# Trottinette_Connexion_PCB.net
KiCad netlist of a schematic drawn in Altium Designer
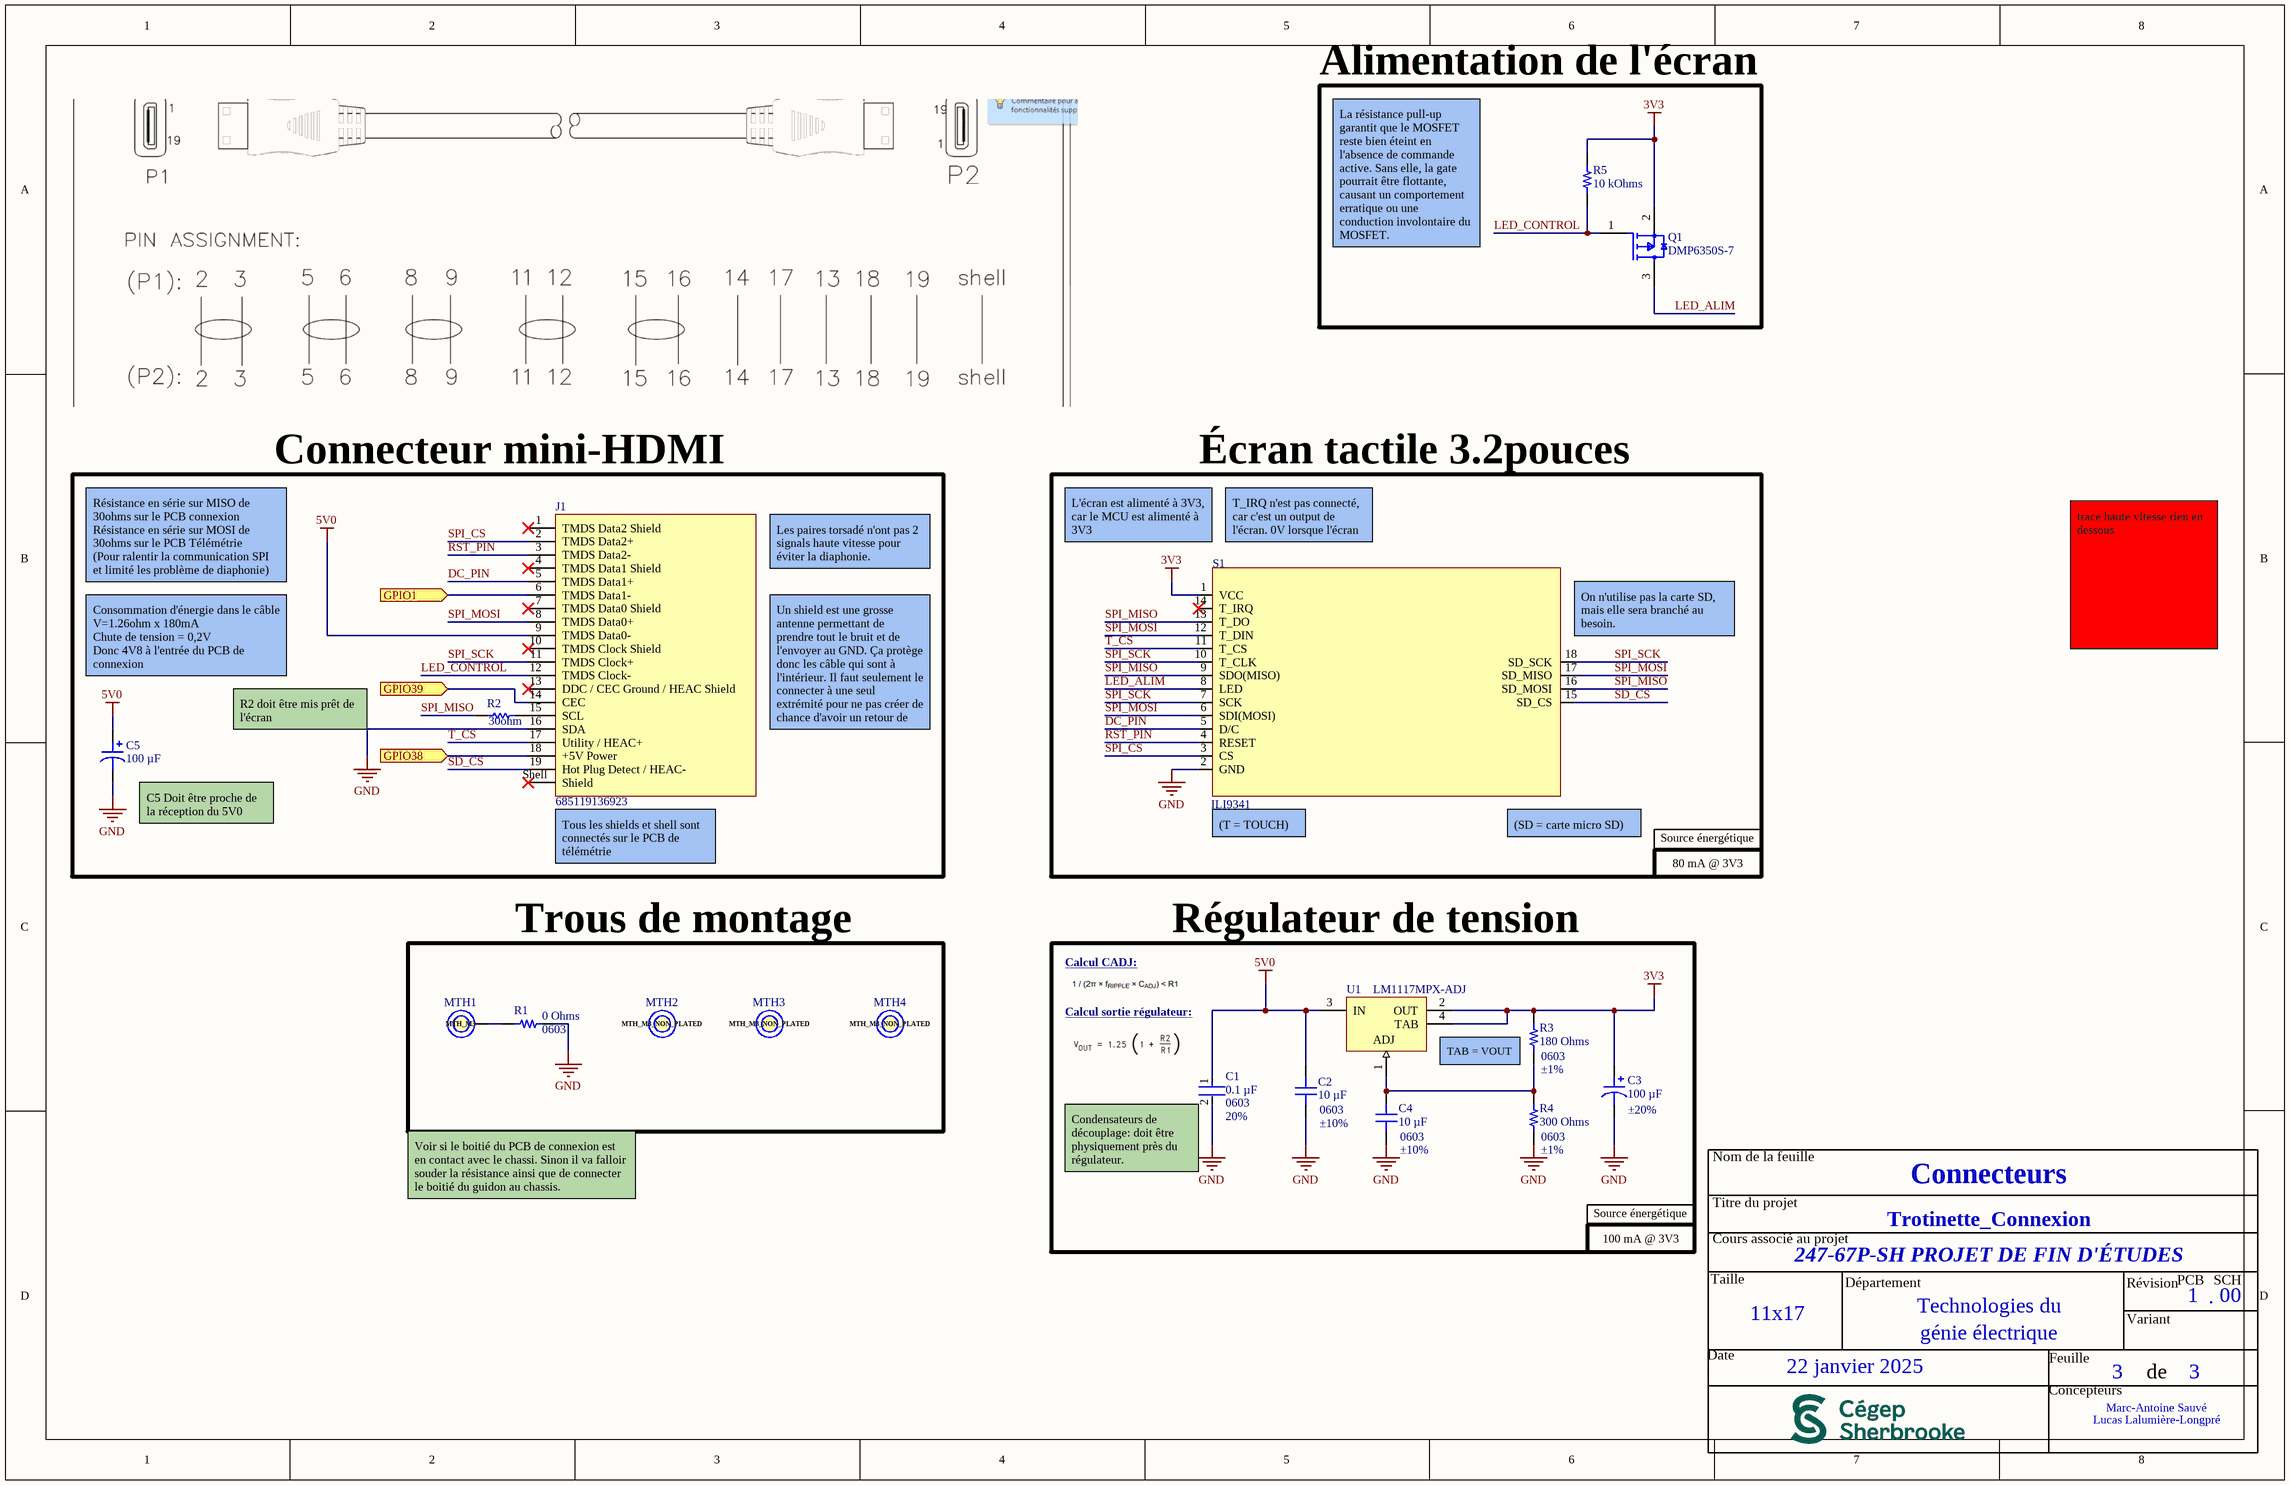
[diagram p0: Trottinette_Connexion_PCB.SchDoc]

(export (version "E")
  (design (tool "Eeschema 10.0.6"))
  (components
    (comp (ref "C1")
      (value "0603ZC104MAT2A")
      (footprint "FP-0603-L_1_6_0_15-W_0_81-IPC_B")
      (description "General Purpose Ceramic Capacitor, 0603, 100nF, 20%, X7R, 15%, 10V")
      (fields
        (field (name "CASE CODE (IMPERIAL)") "0603")
        (field (name "TOLERANCE") "20%")
        (field (name "CAPACITANCE") "0.1 µF")
      )
      (libsource (lib "Altium Content Vault") (part "02cd4be3c70576c341d710602a673aa"))
    )
    (comp (ref "C2")
      (value "10 µF")
      (footprint "CAP 0603_1608")
      (description "CAP CER 10UF 10V X5R 0603")
      (fields
        (field (name "PART NUMBER") "GRT188R61A106KE13D")
        (field (name "DEVICE PACKAGE") "0603")
        (field (name "MANUFACTURER") "Murata Electronics")
        (field (name "TOLERANCE") "±10%")
      )
      (libsource (lib "Celestial Altium Library - altium_library") (part "Capacitor"))
    )
    (comp (ref "C3")
      (value "100 µF")
      (footprint "CAP ALSMD 6.6MM H6.1MM")
      (description "CAP ALUM 100UF 20% 10V SMD")
      (fields
        (field (name "PART NUMBER") "10SGV100M6.3X6.1")
        (field (name "MANUFACTURER") "Rubycon")
        (field (name "TOLERANCE") "±20%")
      )
      (libsource (lib "Celestial Altium Library - altium_library") (part "Polarised Capacitor"))
    )
    (comp (ref "C4")
      (value "10 µF")
      (footprint "CAP 0603_1608")
      (description "CAP CER 10UF 10V X5R 0603")
      (fields
        (field (name "PART NUMBER") "GRT188R61A106KE13D")
        (field (name "DEVICE PACKAGE") "0603")
        (field (name "MANUFACTURER") "Murata Electronics")
        (field (name "TOLERANCE") "±10%")
      )
      (libsource (lib "Celestial Altium Library - altium_library") (part "Capacitor"))
    )
    (comp (ref "C5")
      (value "100 µF")
      (footprint "CAP ALSMD 6.6MM H6.1MM")
      (description "CAP ALUM 100UF 20% 10V SMD")
      (fields (field (name "PART NUMBER") "10SGV100M6.3X6.1") (field (name "MANUFACTURER") "Rubycon"))
      (libsource (lib "Celestial Altium Library - altium_library") (part "Polarised Capacitor"))
    )
    (comp (ref "J1")
      (value "685119136923")
      (footprint "685119136923")
      (libsource (lib "Altium Content Vault") (part "HDMI_Type C"))
    )
    (comp (ref "MTH1")
      (value "MTH_M3")
      (footprint "MTH_M3")
      (description "MTH - MOUNTING HOLE M3 PLATED - M3")
      (fields (field (name "SOURCE") "CEGEP_SHERBROOKE_TGE_LIBRARY.SchLib"))
      (libsource (lib "Cegep de Sherbrooke") (part "MTH_M7"))
    )
    (comp (ref "MTH2")
      (value "MTH_M3_NON_PLATED")
      (footprint "MTH_M3_NON_PLATED")
      (description "MTH - MOUNTING HOLE M3 NON-PLATED - M3")
      (fields (field (name "SOURCE") "CEGEP_SHERBROOKE_TGE_LIBRARY.SchLib"))
      (libsource (lib "Cegep de Sherbrooke") (part "MTH_125MIL_NON-PLATED"))
    )
    (comp (ref "MTH3")
      (value "MTH_M3_NON_PLATED")
      (footprint "MTH_M3_NON_PLATED")
      (description "MTH - MOUNTING HOLE M3 NON-PLATED - M3")
      (fields (field (name "SOURCE") "CEGEP_SHERBROOKE_TGE_LIBRARY.SchLib"))
      (libsource (lib "Cegep de Sherbrooke") (part "MTH_125MIL_NON-PLATED"))
    )
    (comp (ref "MTH4")
      (value "MTH_M3_NON_PLATED")
      (footprint "MTH_M3_NON_PLATED")
      (description "MTH - MOUNTING HOLE M3 NON-PLATED - M3")
      (fields (field (name "SOURCE") "CEGEP_SHERBROOKE_TGE_LIBRARY.SchLib"))
      (libsource (lib "Cegep de Sherbrooke") (part "MTH_125MIL_NON-PLATED"))
    )
    (comp (ref "Q1")
      (value "DMP6350S-7")
      (footprint "FP-SOT23-MFG")
      (description "MOSFET P-CHA 60V 720MW SOT23")
      (libsource (lib "Altium Content Vault") (part "3dbb74db695b7d0c4d5bfcbdbe83ddf"))
    )
    (comp (ref "R1")
      (value "0 Ohms")
      (footprint "RES 0603_1608")
      (description "RESA-AS 0603 0R JUMPER 100MW")
      (fields
        (field (name "PART NUMBER") "CR0603AJ/-000EAS")
        (field (name "MANUFACTURER") "Bourns Inc.")
        (field (name "SUPPLIER DEVICE PACKAGE") "0603")
      )
      (libsource (lib "Celestial Altium Library - altium_library") (part "Resistor"))
    )
    (comp (ref "R2")
      (value "30ohm")
      (footprint "RESC1608X55X30LL15T15")
      (description "30Ohms")
      (fields (field (name "MANUFACTURER") "Panasonic") (field (name "PART NUMBER") "ERJ3EKF30R0V"))
      (libsource (lib "Altium Content Vault") (part "RES"))
    )
    (comp (ref "R3")
      (value "180 Ohms")
      (footprint "RES 0603_1608")
      (description "RES 180 OHM 1% 1/8W 0603")
      (fields
        (field (name "PART NUMBER") "RNCP0603FTD180R")
        (field (name "DEVICE PACKAGE") "0603")
        (field (name "MANUFACTURER") "Stackpole Electronics Inc")
        (field (name "TOLERANCE") "±1%")
      )
      (libsource (lib "Celestial Altium Library - altium_library") (part "Resistor"))
    )
    (comp (ref "R4")
      (value "300 Ohms")
      (footprint "RES 0603_1608")
      (description "RES SMD 300 OHM 1% 1/10W 0603")
      (fields
        (field (name "PART NUMBER") "CRCW0603300RFKEA")
        (field (name "MANUFACTURER") "Vishay Dale")
        (field (name "SUPPLIER DEVICE PACKAGE") "0603")
        (field (name "TOLERANCE") "±1%")
      )
      (libsource (lib "Celestial Altium Library - altium_library") (part "Resistor"))
    )
    (comp (ref "R5")
      (value "10 kOhms")
      (footprint "RES 0603_1608")
      (description "RES 10K OHM 0.1% 1/16W 0603")
      (fields
        (field (name "PART NUMBER") "RNCS0603BKE10K0")
        (field (name "MANUFACTURER") "Stackpole Electronics Inc")
      )
      (libsource (lib "Celestial Altium Library - altium_library") (part "Resistor"))
    )
    (comp (ref "S1")
      (value "ILI9341")
      (footprint "PCBComponent_1")
      (description "3.2\" 240x320 TFT LCD ILI9341")
      (libsource (lib "ILI9341") (part "ILI9341"))
    )
    (comp (ref "U1")
      (value "LM1117MPX-ADJ")
      (footprint "MP04A_N")
      (description "800mA Low-Dropout Linear Regulator, 4-pin SOT-223")
      (fields (field (name "MANUFACTURER") "National Semiconductor"))
      (libsource (lib "Altium Content Vault") (part "PM-REG-LM1086ADJ-SOT4"))
    )
  )
  (nets
    (net (code "1") (name "/DC_PIN") (class "Default")
      (node (ref "J1") (pin "5") (pinfunction "TMDS_Data1+_5") (pintype "passive"))
      (node (ref "S1") (pin "5") (pinfunction "D/C_5") (pintype "passive"))
    )
    (net (code "2") (name "/GPIO1") (class "Default")
      (node (ref "J1") (pin "6") (pinfunction "TMDS_Data1-_6") (pintype "passive"))
    )
    (net (code "3") (name "/GPIO38") (class "Default")
      (node (ref "J1") (pin "18") (pinfunction "+5V_Power_18") (pintype "passive"))
    )
    (net (code "4") (name "/GPIO39") (class "Default")
      (node (ref "J1") (pin "14") (pinfunction "CEC_14") (pintype "passive"))
    )
    (net (code "5") (name "/LED_ALIM") (class "Default")
      (node (ref "Q1") (pin "3") (pinfunction "D_3") (pintype "passive"))
      (node (ref "S1") (pin "8") (pinfunction "LED_8") (pintype "passive"))
    )
    (net (code "6") (name "/LED_CONTROL") (class "Default")
      (node (ref "J1") (pin "12") (pinfunction "TMDS_Clock-_12") (pintype "passive"))
      (node (ref "Q1") (pin "1") (pinfunction "G_1") (pintype "passive"))
      (node (ref "R5") (pin "1") (pinfunction "1_1") (pintype "passive"))
    )
    (net (code "7") (name "/RST_PIN") (class "Default")
      (node (ref "J1") (pin "3") (pinfunction "TMDS_Data2-_3") (pintype "passive"))
      (node (ref "S1") (pin "4") (pinfunction "RESET_4") (pintype "passive"))
    )
    (net (code "8") (name "/SD_CS") (class "Default")
      (node (ref "J1") (pin "19") (pinfunction "Hot_Plug_Detect_/_HEAC-_19") (pintype "passive"))
      (node (ref "S1") (pin "15") (pinfunction "SD_CS_15") (pintype "passive"))
    )
    (net (code "9") (name "/SPI_CS") (class "Default")
      (node (ref "J1") (pin "2") (pinfunction "TMDS_Data2+_2") (pintype "passive"))
      (node (ref "S1") (pin "3") (pinfunction "CS_3") (pintype "passive"))
    )
    (net (code "10") (name "/SPI_MISO") (class "Default")
      (node (ref "R2") (pin "2") (pinfunction "2_2") (pintype "passive"))
      (node (ref "S1") (pin "13") (pinfunction "T_DO_13") (pintype "passive"))
      (node (ref "S1") (pin "16") (pinfunction "SD_MOSI_16") (pintype "passive"))
      (node (ref "S1") (pin "9") (pinfunction "SDO(MISO)_9") (pintype "passive"))
    )
    (net (code "11") (name "/SPI_MOSI") (class "Default")
      (node (ref "J1") (pin "8") (pinfunction "TMDS_Data0+_8") (pintype "passive"))
      (node (ref "S1") (pin "12") (pinfunction "T_DIN_12") (pintype "passive"))
      (node (ref "S1") (pin "17") (pinfunction "SD_MISO_17") (pintype "passive"))
      (node (ref "S1") (pin "6") (pinfunction "SDI(MOSI)_6") (pintype "passive"))
    )
    (net (code "12") (name "/SPI_SCK") (class "Default")
      (node (ref "J1") (pin "11") (pinfunction "TMDS_Clock+_11") (pintype "passive"))
      (node (ref "S1") (pin "10") (pinfunction "T_CLK_10") (pintype "passive"))
      (node (ref "S1") (pin "18") (pinfunction "SD_SCK_18") (pintype "passive"))
      (node (ref "S1") (pin "7") (pinfunction "SCK_7") (pintype "passive"))
    )
    (net (code "13") (name "/T_CS") (class "Default")
      (node (ref "J1") (pin "17") (pinfunction "Utility_/_HEAC+_17") (pintype "passive"))
      (node (ref "S1") (pin "11") (pinfunction "T_CS_11") (pintype "passive"))
    )
    (net (code "14") (name "3V3") (class "Default")
      (node (ref "C3") (pin "1") (pinfunction "1_1") (pintype "passive"))
      (node (ref "Q1") (pin "2") (pinfunction "S_2") (pintype "passive"))
      (node (ref "R3") (pin "2") (pinfunction "2_2") (pintype "passive"))
      (node (ref "R5") (pin "2") (pinfunction "2_2") (pintype "passive"))
      (node (ref "S1") (pin "1") (pinfunction "VCC_1") (pintype "passive"))
      (node (ref "U1") (pin "2") (pinfunction "OUT_2") (pintype "power_in"))
      (node (ref "U1") (pin "4") (pinfunction "TAB_4") (pintype "power_in"))
    )
    (net (code "15") (name "5V0") (class "Default")
      (node (ref "C1") (pin "1") (pinfunction "1_1") (pintype "passive"))
      (node (ref "C2") (pin "2") (pinfunction "2_2") (pintype "passive"))
      (node (ref "C5") (pin "1") (pinfunction "1_1") (pintype "passive"))
      (node (ref "J1") (pin "9") (pinfunction "TMDS_Data0-_9") (pintype "passive"))
      (node (ref "U1") (pin "3") (pinfunction "IN_3") (pintype "power_in"))
    )
    (net (code "16") (name "GND") (class "Default")
      (node (ref "C1") (pin "2") (pinfunction "2_2") (pintype "passive"))
      (node (ref "C2") (pin "1") (pinfunction "1_1") (pintype "passive"))
      (node (ref "C3") (pin "2") (pinfunction "2_2") (pintype "passive"))
      (node (ref "C4") (pin "1") (pinfunction "1_1") (pintype "passive"))
      (node (ref "C5") (pin "2") (pinfunction "2_2") (pintype "passive"))
      (node (ref "J1") (pin "16") (pinfunction "SDA_16") (pintype "passive"))
      (node (ref "R1") (pin "2") (pinfunction "2_2") (pintype "passive"))
      (node (ref "R4") (pin "2") (pinfunction "2_2") (pintype "passive"))
      (node (ref "S1") (pin "2") (pinfunction "GND_2") (pintype "passive"))
    )
    (net (code "17") (name "Net-(J1-SCL)") (class "Default")
      (node (ref "J1") (pin "15") (pinfunction "SCL_15") (pintype "passive"))
      (node (ref "R2") (pin "1") (pinfunction "1_1") (pintype "passive"))
    )
    (net (code "18") (name "Net-(MTH1-Pad1)") (class "Default")
      (node (ref "MTH1") (pin "1") (pinfunction "1_1") (pintype "passive"))
      (node (ref "R1") (pin "1") (pinfunction "1_1") (pintype "passive"))
    )
    (net (code "19") (name "Net-(U1-ADJ)") (class "Default")
      (node (ref "C4") (pin "2") (pinfunction "2_2") (pintype "passive"))
      (node (ref "R3") (pin "1") (pinfunction "1_1") (pintype "passive"))
      (node (ref "R4") (pin "1") (pinfunction "1_1") (pintype "passive"))
      (node (ref "U1") (pin "1") (pinfunction "ADJ_1") (pintype "input"))
    )
    (net (code "20") (name "unconnected-(J1-DDC_{slash}_CEC_Ground_{slash}_HEAC_Shield-Pad13)") (class "Default")
      (node (ref "J1") (pin "13") (pinfunction "DDC_/_CEC_Ground_/_HEAC_Shield_13") (pintype "passive+no_connect"))
    )
    (net (code "21") (name "unconnected-(J1-Shield-PadShell)") (class "Default")
      (node (ref "J1") (pin "Shell") (pinfunction "Shield_Shell") (pintype "passive+no_connect"))
    )
    (net (code "22") (name "unconnected-(J1-TMDS_Clock_Shield-Pad10)") (class "Default")
      (node (ref "J1") (pin "10") (pinfunction "TMDS_Clock_Shield_10") (pintype "passive+no_connect"))
    )
    (net (code "23") (name "unconnected-(J1-TMDS_Data0_Shield-Pad7)") (class "Default")
      (node (ref "J1") (pin "7") (pinfunction "TMDS_Data0_Shield_7") (pintype "passive+no_connect"))
    )
    (net (code "24") (name "unconnected-(J1-TMDS_Data1_Shield-Pad4)") (class "Default")
      (node (ref "J1") (pin "4") (pinfunction "TMDS_Data1_Shield_4") (pintype "passive+no_connect"))
    )
    (net (code "25") (name "unconnected-(J1-TMDS_Data2_Shield-Pad1)") (class "Default")
      (node (ref "J1") (pin "1") (pinfunction "TMDS_Data2_Shield_1") (pintype "passive+no_connect"))
    )
    (net (code "26") (name "unconnected-(S1-T_IRQ-Pad14)") (class "Default")
      (node (ref "S1") (pin "14") (pinfunction "T_IRQ_14") (pintype "passive+no_connect"))
    )
  )
)
